# Tead_Aliens_64A_ESP.net
KiCad netlist of a schematic drawn in Altium Designer
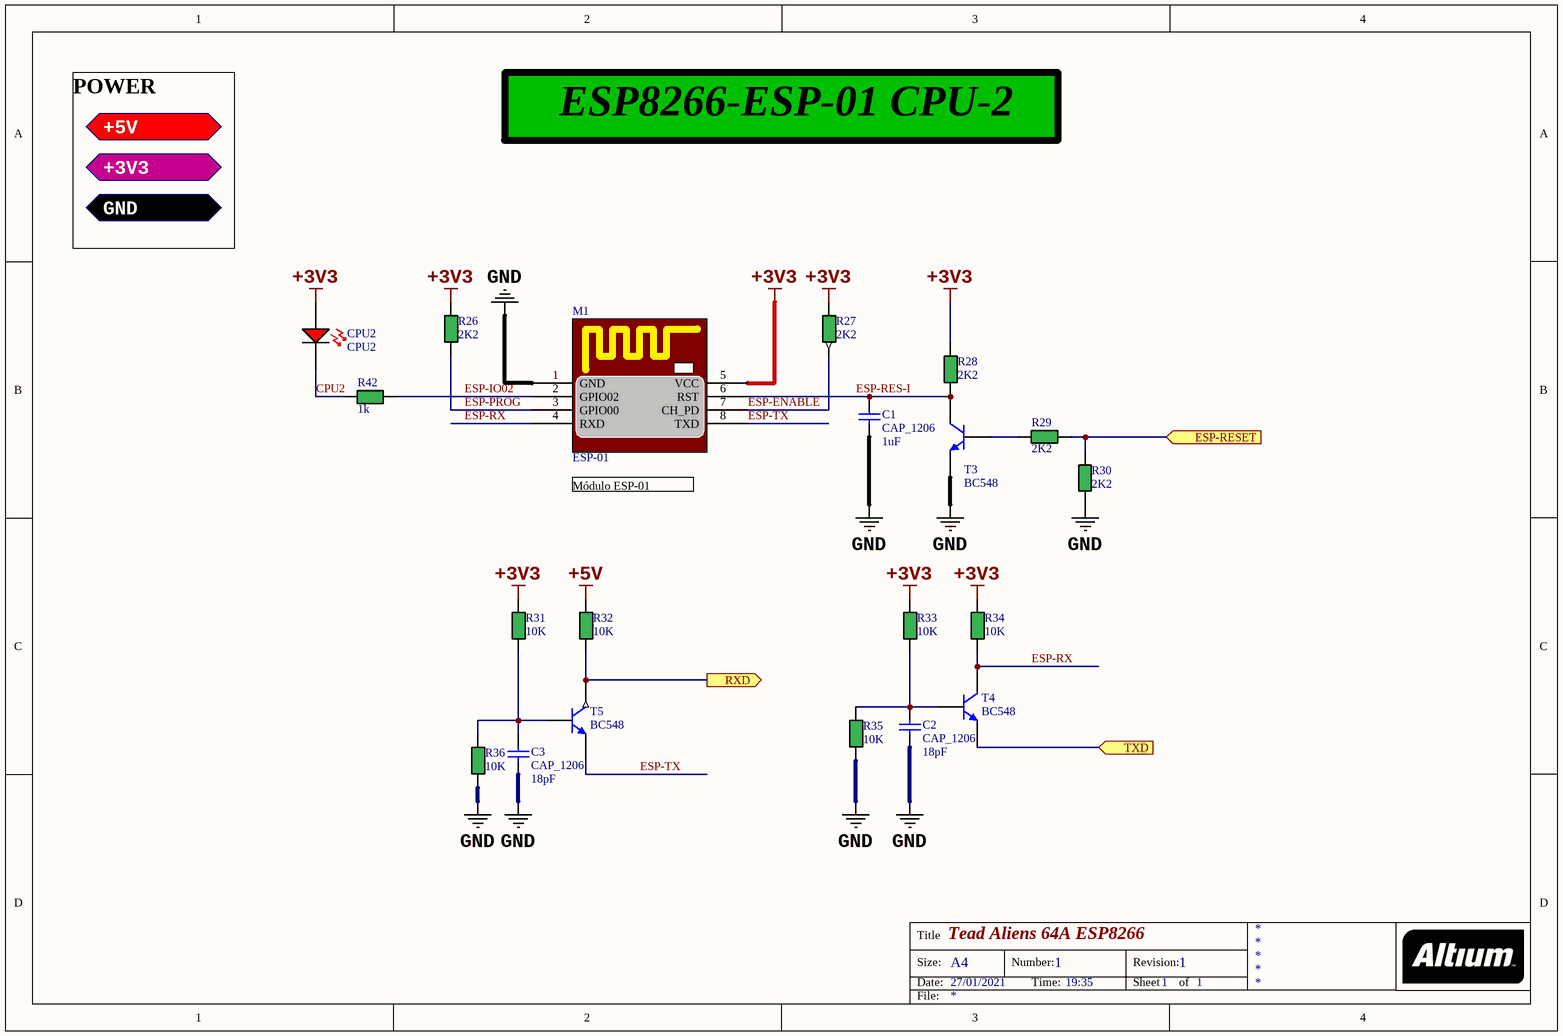
[diagram p0: Tead_Aliens_64A_ESP.SchDoc]

(export (version "E")
  (design (tool "Eeschema 10.0.6"))
  (components
    (comp (ref "C1")
      (value "CAP_1206")
      (footprint "CAP_1206")
      (description "SMD Capacitor 1206 size")
      (fields (field (name "ALTIUM_VALUE") "1uF"))
      (libsource (lib "NEPERMATH") (part "CAP_1206"))
    )
    (comp (ref "C2")
      (value "CAP_1206")
      (footprint "CAP_1206")
      (description "SMD Capacitor 1206 size")
      (fields (field (name "ALTIUM_VALUE") "18pF"))
      (libsource (lib "NEPERMATH") (part "CAP_1206"))
    )
    (comp (ref "C3")
      (value "CAP_1206")
      (footprint "CAP_1206")
      (description "SMD Capacitor 1206 size")
      (fields (field (name "ALTIUM_VALUE") "18pF"))
      (libsource (lib "NEPERMATH") (part "CAP_1206"))
    )
    (comp (ref "CPU2")
      (value "CPU2")
      (footprint "LED Red 3mm")
      (description "LED RED")
      (libsource (lib "NEPERMATH") (part "LED-RED"))
    )
    (comp (ref "M1")
      (value "ESP-01")
      (footprint "ESP-8266-ESP-01")
      (description "ESP8266 ESP-01 Module")
      (libsource (lib "NEPERMATH") (part "ESP-01 Module"))
    )
    (comp (ref "R26")
      (value "2K2")
      (footprint "RES_0805")
      (description "Generic Resistor")
      (fields (field (name "Comment") "Resistor Generic"))
      (libsource (lib "NEPERMATH") (part "Resistor Generic"))
    )
    (comp (ref "R27")
      (value "2K2")
      (footprint "RES_0805")
      (description "Generic Resistor")
      (fields (field (name "Comment") "Resistor Generic"))
      (libsource (lib "NEPERMATH") (part "Resistor Generic"))
    )
    (comp (ref "R28")
      (value "2K2")
      (footprint "RES_0805")
      (description "Generic Resistor")
      (fields (field (name "Comment") "Resistor Generic"))
      (libsource (lib "NEPERMATH") (part "Resistor Generic"))
    )
    (comp (ref "R29")
      (value "2K2")
      (footprint "RES_0805")
      (description "Generic Resistor")
      (fields (field (name "Comment") "Resistor Generic"))
      (libsource (lib "") (part "Resistor Generic_3"))
    )
    (comp (ref "R30")
      (value "2K2")
      (footprint "RES_0805")
      (description "Generic Resistor")
      (fields (field (name "Comment") "Resistor Generic"))
      (libsource (lib "") (part "Resistor Generic_2"))
    )
    (comp (ref "R31")
      (value "10K")
      (footprint "RES_0805")
      (description "Generic Resistor")
      (fields (field (name "Comment") "Resistor Generic"))
      (libsource (lib "NEPERMATH") (part "Resistor Generic"))
    )
    (comp (ref "R32")
      (value "10K")
      (footprint "RES_0805")
      (description "Generic Resistor")
      (fields (field (name "Comment") "Resistor Generic"))
      (libsource (lib "NEPERMATH") (part "Resistor Generic"))
    )
    (comp (ref "R33")
      (value "10K")
      (footprint "RES_0805")
      (description "Generic Resistor")
      (fields (field (name "Comment") "Resistor Generic"))
      (libsource (lib "NEPERMATH") (part "Resistor Generic"))
    )
    (comp (ref "R34")
      (value "10K")
      (footprint "RES_0805")
      (description "Generic Resistor")
      (fields (field (name "Comment") "Resistor Generic"))
      (libsource (lib "NEPERMATH") (part "Resistor Generic"))
    )
    (comp (ref "R35")
      (value "10K")
      (footprint "RES_0805")
      (description "Generic Resistor")
      (fields (field (name "Comment") "Resistor Generic"))
      (libsource (lib "NEPERMATH") (part "Resistor Generic"))
    )
    (comp (ref "R36")
      (value "10K")
      (footprint "RES_0805")
      (description "Generic Resistor")
      (fields (field (name "Comment") "Resistor Generic"))
      (libsource (lib "NEPERMATH") (part "Resistor Generic"))
    )
    (comp (ref "R42")
      (value "1k")
      (footprint "RES_0805")
      (description "Generic Resistor")
      (fields (field (name "Comment") "Resistor Generic"))
      (libsource (lib "") (part "Resistor Generic_1"))
    )
    (comp (ref "T3")
      (value "BC548")
      (footprint "TO-92 - BIG")
      (description "General Bipolar Transistor NPN")
      (fields (field (name "Comment") "Transistor"))
      (libsource (lib "NEPERMATH") (part "T-NPN"))
    )
    (comp (ref "T4")
      (value "BC548")
      (footprint "TO-92 - BIG")
      (description "General Bipolar Transistor NPN")
      (fields (field (name "Comment") "Transistor"))
      (libsource (lib "NEPERMATH") (part "T-NPN"))
    )
    (comp (ref "T5")
      (value "BC548")
      (footprint "TO-92 - BIG")
      (description "General Bipolar Transistor NPN")
      (fields (field (name "Comment") "Transistor"))
      (libsource (lib "NEPERMATH") (part "T-NPN"))
    )
  )
  (nets
    (net (code "1") (name "+3V3") (class "Default")
      (node (ref "CPU2") (pin "A") (pinfunction "A_A") (pintype "passive"))
      (node (ref "M1") (pin "5") (pinfunction "VCC_5") (pintype "power_in"))
      (node (ref "R26") (pin "2") (pinfunction "2_2") (pintype "passive"))
      (node (ref "R27") (pin "2") (pinfunction "2_2") (pintype "passive"))
      (node (ref "R28") (pin "2") (pinfunction "2_2") (pintype "passive"))
      (node (ref "R31") (pin "2") (pinfunction "2_2") (pintype "passive"))
      (node (ref "R33") (pin "2") (pinfunction "2_2") (pintype "passive"))
      (node (ref "R34") (pin "2") (pinfunction "2_2") (pintype "passive"))
    )
    (net (code "2") (name "+5V") (class "Default")
      (node (ref "R32") (pin "2") (pinfunction "2_2") (pintype "passive"))
    )
    (net (code "3") (name "/CPU2") (class "Default")
      (node (ref "CPU2") (pin "K") (pinfunction "K_K") (pintype "passive"))
      (node (ref "R42") (pin "1") (pinfunction "1_1") (pintype "passive"))
    )
    (net (code "4") (name "/ESP-ENABLE") (class "Default")
      (node (ref "M1") (pin "7") (pinfunction "CH_PD_7") (pintype "passive"))
      (node (ref "R27") (pin "1") (pinfunction "1_1") (pintype "passive"))
    )
    (net (code "5") (name "/ESP-IO02") (class "Default")
      (node (ref "M1") (pin "2") (pinfunction "GPIO02_2") (pintype "passive"))
      (node (ref "R42") (pin "2") (pinfunction "2_2") (pintype "passive"))
    )
    (net (code "6") (name "/ESP-PROG") (class "Default")
      (node (ref "M1") (pin "3") (pinfunction "GPIO00_3") (pintype "passive"))
      (node (ref "R26") (pin "1") (pinfunction "1_1") (pintype "passive"))
    )
    (net (code "7") (name "/ESP-RES-I") (class "Default")
      (node (ref "C1") (pin "2") (pinfunction "2_2") (pintype "passive"))
      (node (ref "M1") (pin "6") (pinfunction "RST_6") (pintype "passive"))
      (node (ref "R28") (pin "1") (pinfunction "1_1") (pintype "passive"))
      (node (ref "T3") (pin "3") (pinfunction "C_3") (pintype "passive"))
    )
    (net (code "8") (name "/ESP-RESET") (class "Default")
      (node (ref "R29") (pin "1") (pinfunction "1_1") (pintype "passive"))
      (node (ref "R30") (pin "1") (pinfunction "1_1") (pintype "passive"))
    )
    (net (code "9") (name "/ESP-RX") (class "Default")
      (node (ref "M1") (pin "4") (pinfunction "RXD_4") (pintype "passive"))
      (node (ref "R34") (pin "1") (pinfunction "1_1") (pintype "passive"))
      (node (ref "T4") (pin "3") (pinfunction "C_3") (pintype "passive"))
    )
    (net (code "10") (name "/ESP-TX") (class "Default")
      (node (ref "M1") (pin "8") (pinfunction "TXD_8") (pintype "passive"))
      (node (ref "T5") (pin "1") (pinfunction "E_1") (pintype "passive"))
    )
    (net (code "11") (name "/RXD") (class "Default")
      (node (ref "R32") (pin "1") (pinfunction "1_1") (pintype "passive"))
      (node (ref "T5") (pin "3") (pinfunction "C_3") (pintype "passive"))
    )
    (net (code "12") (name "/TXD") (class "Default")
      (node (ref "T4") (pin "1") (pinfunction "E_1") (pintype "passive"))
    )
    (net (code "13") (name "GND") (class "Default")
      (node (ref "C1") (pin "1") (pinfunction "1_1") (pintype "passive"))
      (node (ref "C2") (pin "1") (pinfunction "1_1") (pintype "passive"))
      (node (ref "C3") (pin "1") (pinfunction "1_1") (pintype "passive"))
      (node (ref "M1") (pin "1") (pinfunction "GND_1") (pintype "power_in"))
      (node (ref "R30") (pin "2") (pinfunction "2_2") (pintype "passive"))
      (node (ref "R35") (pin "1") (pinfunction "1_1") (pintype "passive"))
      (node (ref "R36") (pin "1") (pinfunction "1_1") (pintype "passive"))
      (node (ref "T3") (pin "1") (pinfunction "E_1") (pintype "passive"))
    )
    (net (code "14") (name "Net-(T3-B)") (class "Default")
      (node (ref "R29") (pin "2") (pinfunction "2_2") (pintype "passive"))
      (node (ref "T3") (pin "2") (pinfunction "B_2") (pintype "passive"))
    )
    (net (code "15") (name "Net-(T4-B)") (class "Default")
      (node (ref "C2") (pin "2") (pinfunction "2_2") (pintype "passive"))
      (node (ref "R33") (pin "1") (pinfunction "1_1") (pintype "passive"))
      (node (ref "R35") (pin "2") (pinfunction "2_2") (pintype "passive"))
      (node (ref "T4") (pin "2") (pinfunction "B_2") (pintype "passive"))
    )
    (net (code "16") (name "Net-(T5-B)") (class "Default")
      (node (ref "C3") (pin "2") (pinfunction "2_2") (pintype "passive"))
      (node (ref "R31") (pin "1") (pinfunction "1_1") (pintype "passive"))
      (node (ref "R36") (pin "2") (pinfunction "2_2") (pintype "passive"))
      (node (ref "T5") (pin "2") (pinfunction "B_2") (pintype "passive"))
    )
  )
)
